# A_OUTPUT.net
KiCad netlist of a schematic drawn in Altium Designer
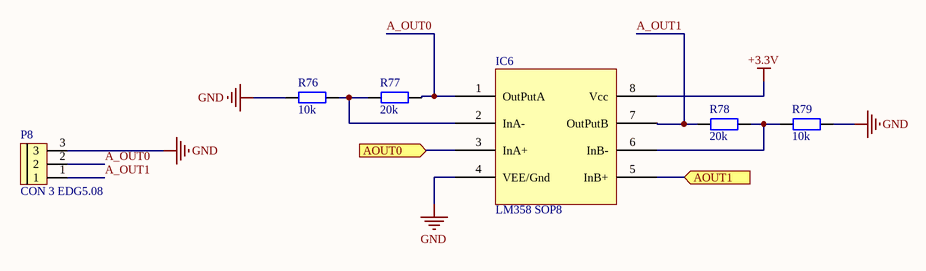
[diagram p0: A_OUTPUT.SchDoc]

(export (version "E")
  (design (tool "Eeschema 10.0.6"))
  (components
    (comp (ref "IC6")
      (value "LM358 SOP8")
      (footprint "SOP 8")
      (description "Dán")
      (libsource (lib "Altium_Lib_by_KhueNguyenCreator") (part "LM358 SOP8"))
    )
    (comp (ref "P8")
      (value "CON 3 EDG5.08")
      (footprint "CON 3 3EDG5.08")
      (description "Cắm")
      (libsource (lib "Altium_Lib_by_KhueNguyenCreator") (part "CON 3 EDG5.08"))
    )
    (comp (ref "R76")
      (value "10k")
      (footprint "tro smd 0805")
      (description "Dán")
      (libsource (lib "Altium_Lib_by_KhueNguyenCreator") (part "Tro 0805 1% 10k"))
    )
    (comp (ref "R77")
      (value "20k")
      (footprint "tro smd 0805")
      (description "Dán")
      (libsource (lib "Altium_Lib_by_KhueNguyenCreator") (part "Tro 0805 1% 10k"))
    )
    (comp (ref "R78")
      (value "20k")
      (footprint "tro smd 0805")
      (description "Dán")
      (libsource (lib "Altium_Lib_by_KhueNguyenCreator") (part "Tro 0805 1% 10k"))
    )
    (comp (ref "R79")
      (value "10k")
      (footprint "tro smd 0805")
      (description "Dán")
      (libsource (lib "Altium_Lib_by_KhueNguyenCreator") (part "Tro 0805 1% 10k"))
    )
  )
  (nets
    (net (code "1") (name "+3.3V") (class "Default")
      (node (ref "IC6") (pin "8") (pinfunction "Vcc_8") (pintype "passive"))
    )
    (net (code "2") (name "/AOUT0") (class "Default")
      (node (ref "IC6") (pin "3") (pinfunction "InA+_3") (pintype "passive"))
    )
    (net (code "3") (name "/AOUT1") (class "Default")
      (node (ref "IC6") (pin "5") (pinfunction "InB+_5") (pintype "passive"))
    )
    (net (code "4") (name "/A_OUT0") (class "Default")
      (node (ref "IC6") (pin "1") (pinfunction "OutPutA_1") (pintype "passive"))
      (node (ref "P8") (pin "2") (pinfunction "2_2") (pintype "passive"))
      (node (ref "R77") (pin "2") (pinfunction "2_2") (pintype "passive"))
    )
    (net (code "5") (name "/A_OUT1") (class "Default")
      (node (ref "IC6") (pin "7") (pinfunction "OutPutB_7") (pintype "passive"))
      (node (ref "P8") (pin "1") (pinfunction "1_1") (pintype "passive"))
      (node (ref "R78") (pin "2") (pinfunction "2_2") (pintype "passive"))
    )
    (net (code "6") (name "GND") (class "Default")
      (node (ref "IC6") (pin "4") (pinfunction "VEE/Gnd_4") (pintype "passive"))
      (node (ref "P8") (pin "3") (pinfunction "3_3") (pintype "passive"))
      (node (ref "R76") (pin "1") (pinfunction "1_1") (pintype "passive"))
      (node (ref "R79") (pin "1") (pinfunction "1_1") (pintype "passive"))
    )
    (net (code "7") (name "Net-(IC6-InA-)") (class "Default")
      (node (ref "IC6") (pin "2") (pinfunction "InA-_2") (pintype "passive"))
      (node (ref "R76") (pin "2") (pinfunction "2_2") (pintype "passive"))
      (node (ref "R77") (pin "1") (pinfunction "1_1") (pintype "passive"))
    )
    (net (code "8") (name "Net-(IC6-InB-)") (class "Default")
      (node (ref "IC6") (pin "6") (pinfunction "InB-_6") (pintype "passive"))
      (node (ref "R78") (pin "1") (pinfunction "1_1") (pintype "passive"))
      (node (ref "R79") (pin "2") (pinfunction "2_2") (pintype "passive"))
    )
  )
)
